# H2BR1.net
KiCad netlist of a schematic drawn in EAGLE
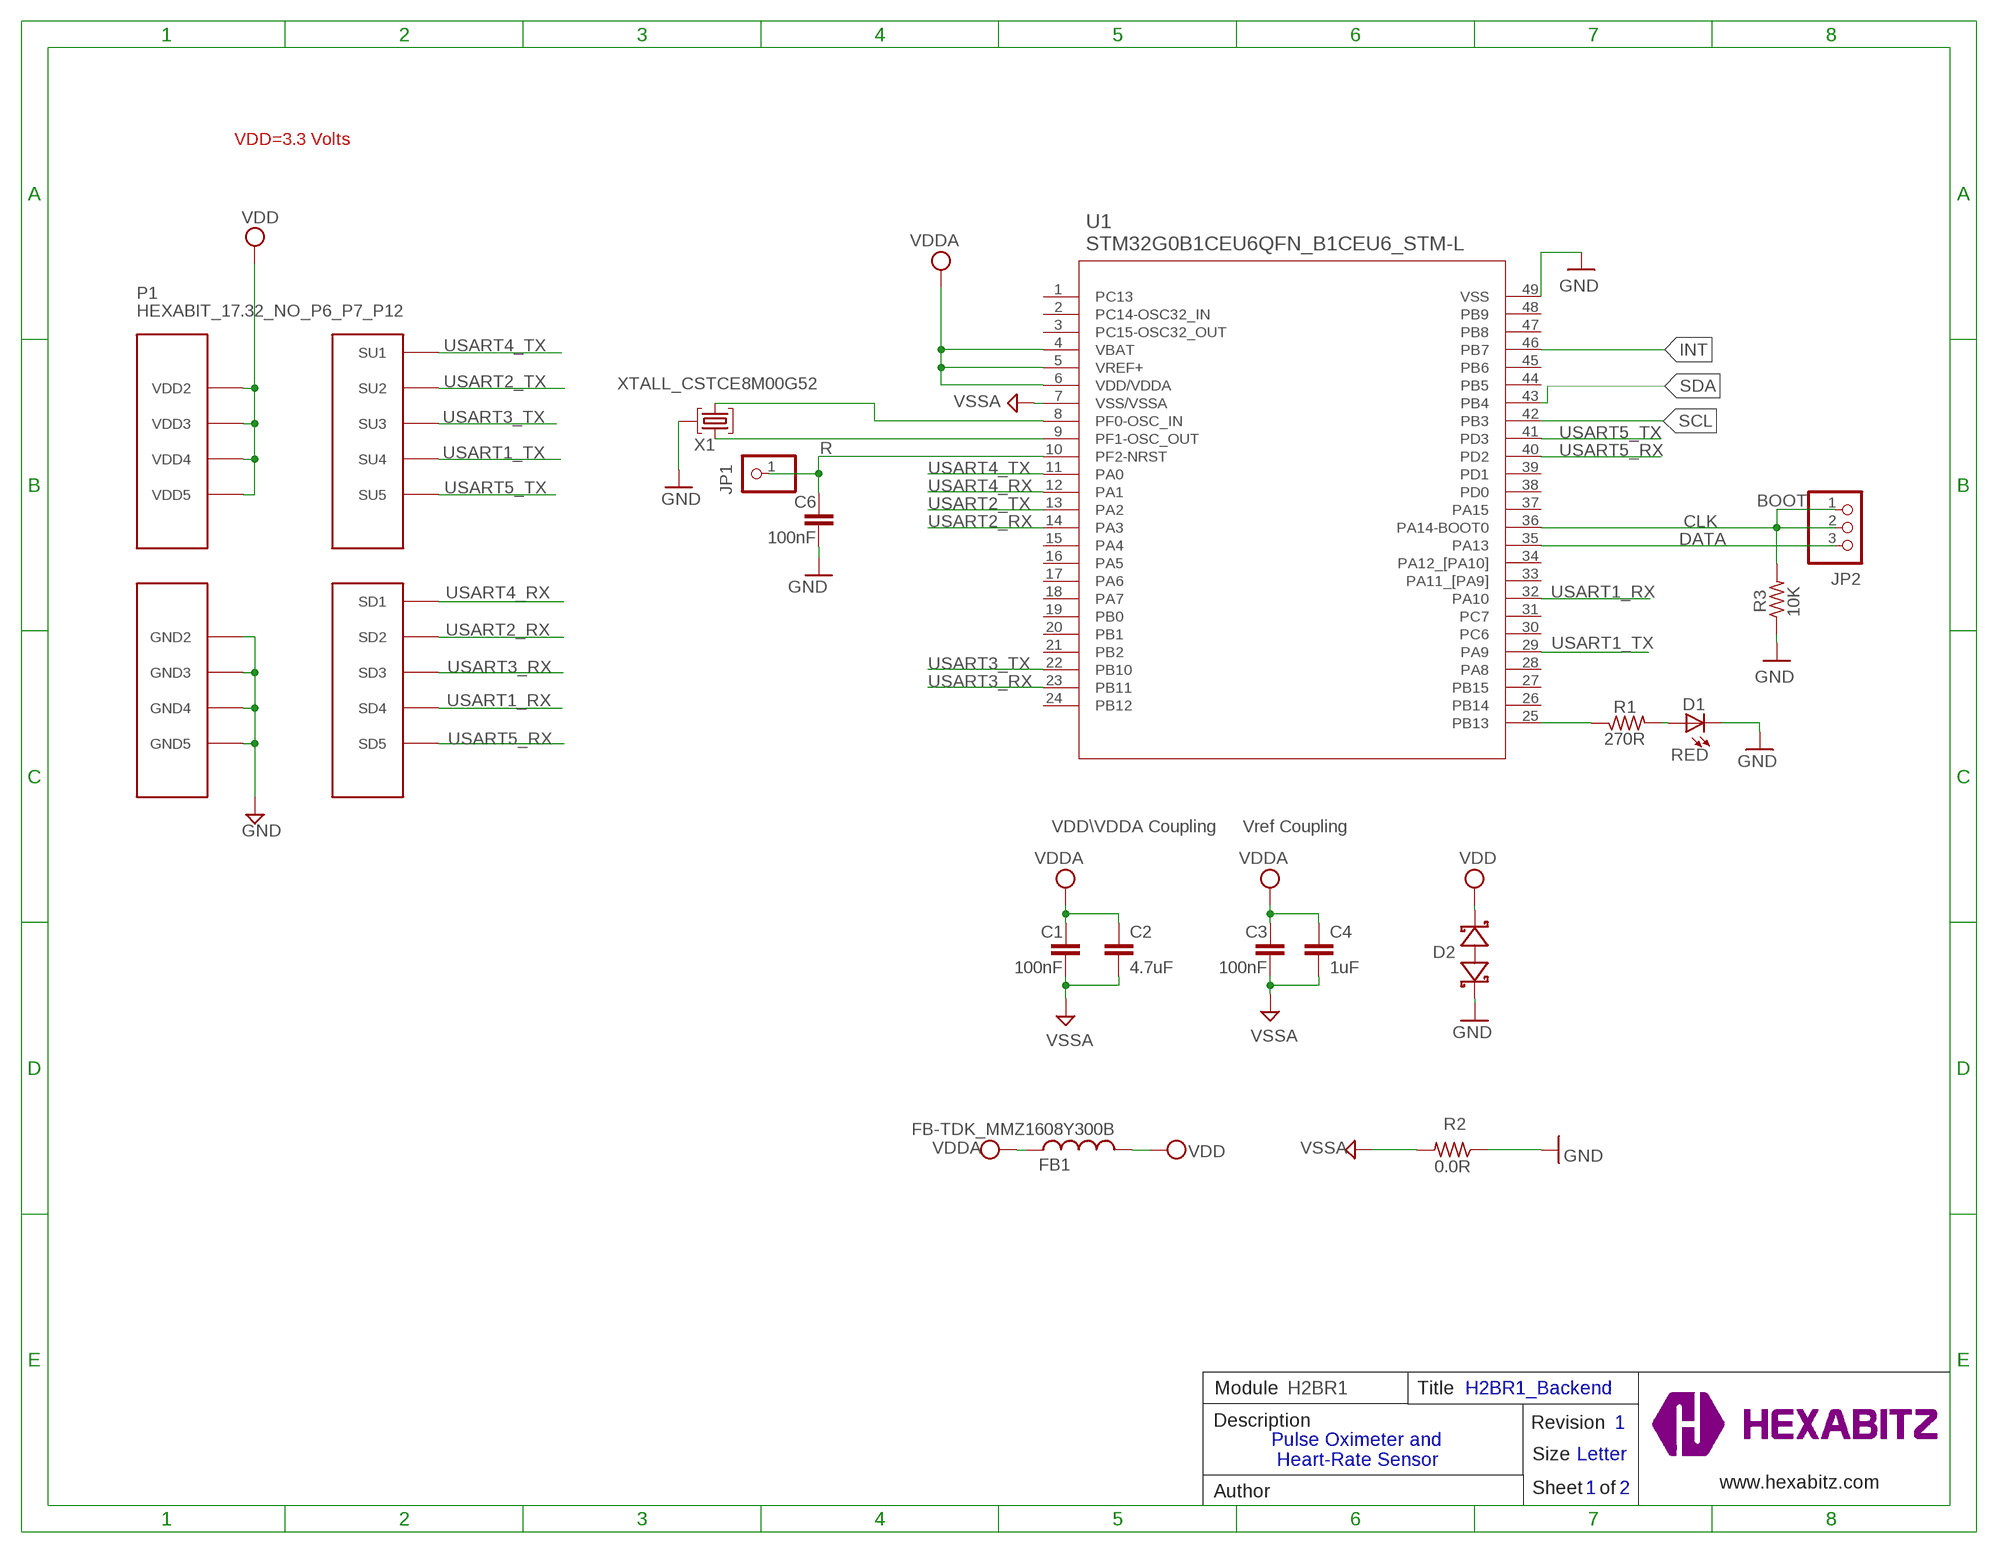
[diagram p0: schematic, sheet 1]
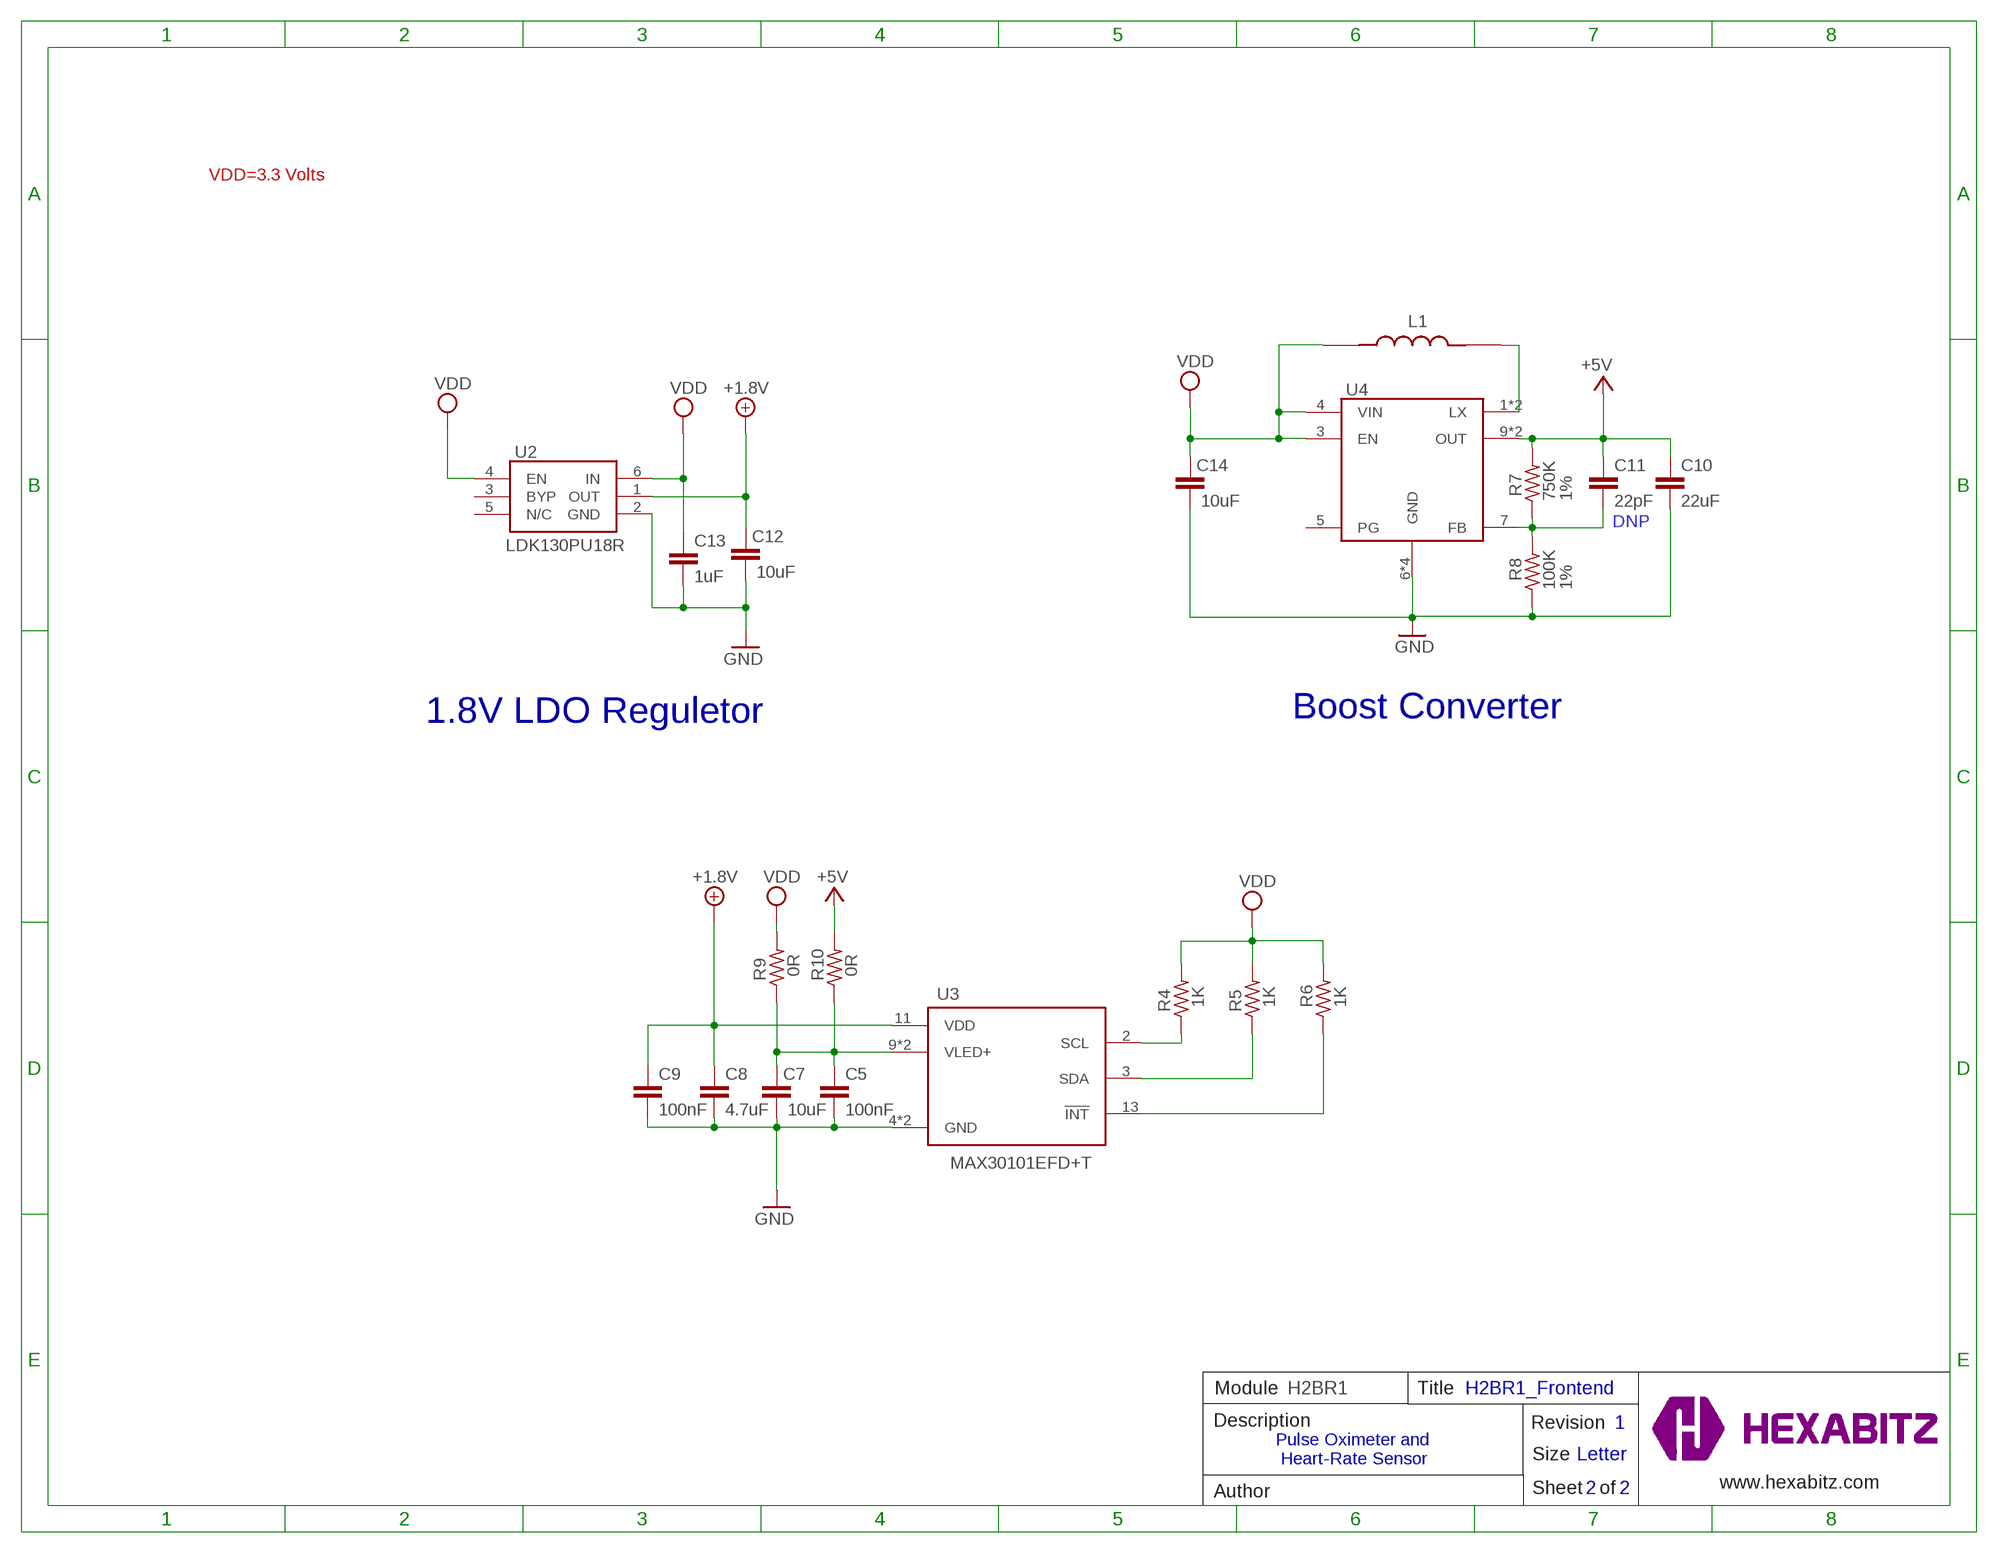
[diagram p1: schematic, sheet 2]

(export (version "E")
  (design (tool "Eeschema 10.0.6"))
  (components
    (comp (ref "C5")
      (value "100nF")
      (footprint "eagle-import:C-0603")
      (libsource (lib "eagle-import") (part "C-0603"))
    )
    (comp (ref "C7")
      (value "10uF")
      (footprint "eagle-import:C-0805")
      (libsource (lib "eagle-import") (part "C-0805"))
    )
    (comp (ref "C8")
      (value "4.7uF")
      (footprint "eagle-import:C-0805")
      (libsource (lib "eagle-import") (part "C-0805"))
    )
    (comp (ref "C9")
      (value "100nF")
      (footprint "eagle-import:C-0603")
      (libsource (lib "eagle-import") (part "C-0603"))
    )
    (comp (ref "C10")
      (value "22uF")
      (footprint "eagle-import:C-0603")
      (libsource (lib "eagle-import") (part "C-0603"))
    )
    (comp (ref "C11")
      (value "22pF")
      (footprint "eagle-import:C-0603")
      (fields (field (name "STATUS") "DNP"))
      (libsource (lib "eagle-import") (part "C-0603"))
    )
    (comp (ref "C12")
      (value "10uF")
      (footprint "eagle-import:C-0805")
      (libsource (lib "eagle-import") (part "C-0805"))
    )
    (comp (ref "C13")
      (value "1uF")
      (footprint "eagle-import:C-0805")
      (libsource (lib "eagle-import") (part "C-0805"))
    )
    (comp (ref "C14")
      (value "10uF")
      (footprint "eagle-import:C-0805")
      (libsource (lib "eagle-import") (part "C-0805"))
    )
    (comp (ref "L1")
      (value "ASMPH08062R2MT")
      (footprint "eagle-import:INDC1608X95N")
      (fields (field (name "MPN") "ASMPH-0806-2R2M-T"))
      (libsource (lib "eagle-import") (part "ASMPH08062R2MT"))
    )
    (comp (ref "R4")
      (value "1K")
      (footprint "eagle-import:R-0603")
      (libsource (lib "eagle-import") (part "R-0603"))
    )
    (comp (ref "R5")
      (value "1K")
      (footprint "eagle-import:R-0603")
      (libsource (lib "eagle-import") (part "R-0603"))
    )
    (comp (ref "R6")
      (value "1K")
      (footprint "eagle-import:R-0603")
      (libsource (lib "eagle-import") (part "R-0603"))
    )
    (comp (ref "R7")
      (value "750K")
      (footprint "eagle-import:R-0603")
      (fields (field (name "TOLERANCE") "1%"))
      (libsource (lib "eagle-import") (part "R-0603"))
    )
    (comp (ref "R8")
      (value "100K")
      (footprint "eagle-import:R-0603")
      (fields (field (name "TOLERANCE") "1%"))
      (libsource (lib "eagle-import") (part "R-0603"))
    )
    (comp (ref "R9")
      (value "0R")
      (footprint "eagle-import:R-0603")
      (libsource (lib "eagle-import") (part "R-0603"))
    )
    (comp (ref "R10")
      (value "0R")
      (footprint "eagle-import:R-0603")
      (libsource (lib "eagle-import") (part "R-0603"))
    )
    (comp (ref "U2")
      (value "LDK130PU18R")
      (footprint "eagle-import:LDK130PU18R")
      (fields (field (name "MOUSER_PART_NUMBER") "511-LDK130PU18R"))
      (libsource (lib "eagle-import") (part "LDK130PU18R"))
    )
    (comp (ref "U3")
      (value "MAX30101EFD+T")
      (footprint "eagle-import:14-LEAD-OESIP")
      (fields (field (name "MOUSER_PART_NUMBER") "700-MAX30101EFD+T"))
      (libsource (lib "eagle-import") (part "MAX30101EFD+T"))
    )
    (comp (ref "U4")
      (value "PAM2401YPADJ")
      (footprint "eagle-import:SON45P300X300X63-13N")
      (fields (field (name "MOUSER_PART_NUMBER") "621-PAM2401YPADJ"))
      (libsource (lib "eagle-import") (part "PAM2401YPADJ"))
    )
    (comp (ref "C1")
      (value "100nF")
      (footprint "eagle-import:C-0603")
      (libsource (lib "eagle-import") (part "C-0603"))
    )
    (comp (ref "C2")
      (value "4.7uF")
      (footprint "eagle-import:C-0805")
      (libsource (lib "eagle-import") (part "C-0805"))
    )
    (comp (ref "C3")
      (value "100nF")
      (footprint "eagle-import:C-0603")
      (libsource (lib "eagle-import") (part "C-0603"))
    )
    (comp (ref "C4")
      (value "1uF")
      (footprint "eagle-import:C-0805")
      (libsource (lib "eagle-import") (part "C-0805"))
    )
    (comp (ref "C6")
      (value "100nF")
      (footprint "eagle-import:C-0603")
      (libsource (lib "eagle-import") (part "C-0603"))
    )
    (comp (ref "D1")
      (value "RED")
      (footprint "eagle-import:VLMS1300-GS08")
      (fields
        (field (name "MPN") "VLMS1300-GS08")
        (field (name "MFN") "Vishay")
        (field (name "MPN_1") "VLMS1300-GS08")
        (field (name "OCTOPART_URL") "https://octopart.com/vlms1300-gs08-vishay-21709201?r=sp&s=_gcP4_q8T1SC6PJQPTQ9yA")
      )
      (libsource (lib "eagle-import") (part "VLMS1300-GS08"))
    )
    (comp (ref "D2")
      (value "BOURNS_CDSOD323-T03SCBOURNS_CDSOD323-T03SC_0_0")
      (footprint "eagle-import:BOURNS_CDSOD323-T03SC_0")
      (fields (field (name "MPN") "CDSOD323-T03SC"))
      (libsource (lib "eagle-import") (part "BOURNS_CDSOD323-T03SCBOURNS_CDSOD323-T03SC_0_0"))
    )
    (comp (ref "FB1")
      (value "FB-TDK_MMZ1608Y300B")
      (footprint "eagle-import:FB-0603")
      (fields
        (field (name "MFN") "TDK ")
        (field (name "MPN") "MMZ1608Y300B")
        (field (name "OCTOPART_URL") "https://octopart.com/mmz1608y300b-tdk-368280?r=sp&s=cd9_2ZEqQ9q9UNBuQgHAiA")
      )
      (libsource (lib "eagle-import") (part "FB-0603"))
    )
    (comp (ref "JP1")
      (value "R")
      (footprint "eagle-import:1X01")
      (fields (field (name "MPN") "87227-1"))
      (libsource (lib "eagle-import") (part "PINHD-1X1"))
    )
    (comp (ref "JP2")
      (value "PINHD-1X3")
      (footprint "eagle-import:1X03")
      (libsource (lib "eagle-import") (part "PINHD-1X3"))
    )
    (comp (ref "P1")
      (value "HEXABIT_17.32_NO_P6_P7_P12")
      (footprint "eagle-import:HEXABIT_17.32_NO_P6_P7_P12")
      (libsource (lib "eagle-import") (part "HEXABIT_?_NO_P6_P7_P1217.32"))
    )
    (comp (ref "R1")
      (value "270R")
      (footprint "eagle-import:R-0603")
      (libsource (lib "eagle-import") (part "R-0603"))
    )
    (comp (ref "R2")
      (value "0.0R")
      (footprint "eagle-import:R-0603")
      (fields
        (field (name "MFN") "Yageo")
        (field (name "MPN") "RC0603JR-070RL")
        (field (name "OCTOPART_URL") "https://octopart.com/rc0603jr-070rl-yageo-1241539?r=sp&s=X2NteqRjRNWrnx42Y0aliA")
        (field (name "RESISTANCE") "0.0 Ohm")
      )
      (libsource (lib "eagle-import") (part "R-0603"))
    )
    (comp (ref "R3")
      (value "10K")
      (footprint "eagle-import:R-0603")
      (libsource (lib "eagle-import") (part "R-0603"))
    )
    (comp (ref "TRIMBLE-LOGO1")
      (value "HEXA-LOGO")
      (footprint "eagle-import:HEXA-LOGO")
      (libsource (lib "eagle-import") (part "HEXA-LOGO"))
    )
    (comp (ref "U1")
      (value "STM32G0B1CEU6QFN_B1CEU6_STM-L")
      (footprint "eagle-import:QFN_B1CEU6_STM-L")
      (fields
        (field (name "MANUFACTURER_PART_NUMBER") "STM32G0B1CEU6")
        (field (name "COPYRIGHT") "Copyright (C) 2021 Ultra Librarian. All rights reserved.")
      )
      (libsource (lib "eagle-import") (part "STM32G0B1CEU6QFN_B1CEU6_STM-L"))
    )
    (comp (ref "X1")
      (value "XTALL_CSTCE8M00G52")
      (footprint "eagle-import:XTALL_CSTCE8M00G52")
      (fields (field (name "MPN") "CSTCE8M00G52Z-R0"))
      (libsource (lib "eagle-import") (part "XTALL_CSTCE8M00G52"))
    )
  )
  (nets
    (net (code "1") (name "+1.8V") (class "Default")
      (node (ref "C12") (pin "1") (pinfunction "1_1") (pintype "passive"))
      (node (ref "C8") (pin "1") (pinfunction "1_1") (pintype "passive"))
      (node (ref "C9") (pin "1") (pinfunction "1_1") (pintype "passive"))
      (node (ref "U2") (pin "1") (pinfunction "OUT_1") (pintype "bidirectional"))
      (node (ref "U3") (pin "11") (pinfunction "VDD_11") (pintype "bidirectional"))
    )
    (net (code "2") (name "+5V") (class "Default")
      (node (ref "C10") (pin "1") (pinfunction "1_1") (pintype "passive"))
      (node (ref "C11") (pin "1") (pinfunction "1_1") (pintype "passive"))
      (node (ref "R10") (pin "2") (pinfunction "2_2") (pintype "passive"))
      (node (ref "R7") (pin "2") (pinfunction "2_2") (pintype "passive"))
      (node (ref "U4") (pin "10") (pinfunction "OUT_10") (pintype "bidirectional"))
      (node (ref "U4") (pin "9") (pinfunction "OUT_9") (pintype "bidirectional"))
    )
    (net (code "3") (name "CLK") (class "Default")
      (node (ref "JP2") (pin "1") (pinfunction "1_1") (pintype "passive"))
      (node (ref "JP2") (pin "2") (pinfunction "2_2") (pintype "passive"))
      (node (ref "R3") (pin "2") (pinfunction "2_2") (pintype "passive"))
      (node (ref "U1") (pin "36") (pinfunction "PA14-BOOT0_36") (pintype "bidirectional"))
    )
    (net (code "4") (name "DATA") (class "Default")
      (node (ref "JP2") (pin "3") (pinfunction "3_3") (pintype "passive"))
      (node (ref "U1") (pin "35") (pinfunction "PA13_35") (pintype "bidirectional"))
    )
    (net (code "5") (name "GND") (class "Default")
      (node (ref "C10") (pin "2") (pinfunction "2_2") (pintype "passive"))
      (node (ref "C12") (pin "2") (pinfunction "2_2") (pintype "passive"))
      (node (ref "C13") (pin "2") (pinfunction "2_2") (pintype "passive"))
      (node (ref "C14") (pin "2") (pinfunction "2_2") (pintype "passive"))
      (node (ref "C5") (pin "2") (pinfunction "2_2") (pintype "passive"))
      (node (ref "C6") (pin "2") (pinfunction "2_2") (pintype "passive"))
      (node (ref "C7") (pin "2") (pinfunction "2_2") (pintype "passive"))
      (node (ref "C8") (pin "2") (pinfunction "2_2") (pintype "passive"))
      (node (ref "C9") (pin "2") (pinfunction "2_2") (pintype "passive"))
      (node (ref "D1") (pin "C") (pinfunction "C_C") (pintype "passive"))
      (node (ref "D2") (pin "1") (pinfunction "A_1") (pintype "passive"))
      (node (ref "P1") (pin "PAD_PD10") (pinfunction "GND4_PAD_PD10") (pintype "power_in"))
      (node (ref "P1") (pin "PAD_PD11") (pinfunction "GND5_PAD_PD11") (pintype "power_in"))
      (node (ref "P1") (pin "PAD_PD8") (pinfunction "GND2_PAD_PD8") (pintype "power_in"))
      (node (ref "P1") (pin "PAD_PD9") (pinfunction "GND3_PAD_PD9") (pintype "power_in"))
      (node (ref "R2") (pin "1") (pinfunction "1_1") (pintype "passive"))
      (node (ref "R3") (pin "1") (pinfunction "1_1") (pintype "passive"))
      (node (ref "R8") (pin "1") (pinfunction "1_1") (pintype "passive"))
      (node (ref "U1") (pin "49") (pinfunction "VSS_49") (pintype "passive"))
      (node (ref "U2") (pin "2") (pinfunction "GND_2") (pintype "bidirectional"))
      (node (ref "U3") (pin "12") (pinfunction "GND_12") (pintype "bidirectional"))
      (node (ref "U3") (pin "4") (pinfunction "GND_4") (pintype "bidirectional"))
      (node (ref "U4") (pin "11") (pinfunction "GND_11") (pintype "bidirectional"))
      (node (ref "U4") (pin "12") (pinfunction "GND_12") (pintype "bidirectional"))
      (node (ref "U4") (pin "13") (pinfunction "GND_13") (pintype "bidirectional"))
      (node (ref "U4") (pin "6") (pinfunction "GND_6") (pintype "bidirectional"))
      (node (ref "X1") (pin "P$2") (pinfunction "2_P$2") (pintype "passive"))
    )
    (net (code "6") (name "INT") (class "Default")
      (node (ref "R6") (pin "1") (pinfunction "1_1") (pintype "passive"))
      (node (ref "U1") (pin "46") (pinfunction "PB7_46") (pintype "bidirectional"))
      (node (ref "U3") (pin "13") (pinfunction "~{INT}_13") (pintype "bidirectional"))
    )
    (net (code "7") (name "Net-(C5-Pad1)") (class "Default")
      (node (ref "C5") (pin "1") (pinfunction "1_1") (pintype "passive"))
      (node (ref "C7") (pin "1") (pinfunction "1_1") (pintype "passive"))
      (node (ref "R10") (pin "1") (pinfunction "1_1") (pintype "passive"))
      (node (ref "R9") (pin "1") (pinfunction "1_1") (pintype "passive"))
      (node (ref "U3") (pin "10") (pinfunction "VLED+_10") (pintype "bidirectional"))
      (node (ref "U3") (pin "9") (pinfunction "VLED+_9") (pintype "bidirectional"))
    )
    (net (code "8") (name "Net-(D1-PadA)") (class "Default")
      (node (ref "D1") (pin "A") (pinfunction "A_A") (pintype "passive"))
      (node (ref "R1") (pin "2") (pinfunction "2_2") (pintype "passive"))
    )
    (net (code "9") (name "Net-(L1-Pad2)") (class "Default")
      (node (ref "L1") (pin "2") (pinfunction "2_2") (pintype "passive"))
      (node (ref "U4") (pin "1") (pinfunction "LX_1") (pintype "bidirectional"))
      (node (ref "U4") (pin "2") (pinfunction "LX_2") (pintype "bidirectional"))
    )
    (net (code "10") (name "Net-(U1-PB13)") (class "Default")
      (node (ref "R1") (pin "1") (pinfunction "1_1") (pintype "passive"))
      (node (ref "U1") (pin "25") (pinfunction "PB13_25") (pintype "bidirectional"))
    )
    (net (code "11") (name "Net-(U1-PF0-OSC_IN)") (class "Default")
      (node (ref "U1") (pin "8") (pinfunction "PF0-OSC_IN_8") (pintype "bidirectional"))
      (node (ref "X1") (pin "P$3") (pinfunction "3_P$3") (pintype "passive"))
    )
    (net (code "12") (name "Net-(U1-PF1-OSC_OUT)") (class "Default")
      (node (ref "U1") (pin "9") (pinfunction "PF1-OSC_OUT_9") (pintype "output"))
      (node (ref "X1") (pin "P$1") (pinfunction "1_P$1") (pintype "passive"))
    )
    (net (code "13") (name "Net-(U1-PF2-NRST)") (class "Default")
      (node (ref "C6") (pin "1") (pinfunction "1_1") (pintype "passive"))
      (node (ref "JP1") (pin "1") (pinfunction "1_1") (pintype "passive"))
      (node (ref "U1") (pin "10") (pinfunction "PF2-NRST_10") (pintype "bidirectional"))
    )
    (net (code "14") (name "Net-(U4-FB)") (class "Default")
      (node (ref "C11") (pin "2") (pinfunction "2_2") (pintype "passive"))
      (node (ref "R7") (pin "1") (pinfunction "1_1") (pintype "passive"))
      (node (ref "R8") (pin "2") (pinfunction "2_2") (pintype "passive"))
      (node (ref "U4") (pin "7") (pinfunction "FB_7") (pintype "bidirectional"))
    )
    (net (code "15") (name "SCL") (class "Default")
      (node (ref "R4") (pin "1") (pinfunction "1_1") (pintype "passive"))
      (node (ref "U1") (pin "42") (pinfunction "PB3_42") (pintype "bidirectional"))
      (node (ref "U3") (pin "2") (pinfunction "SCL_2") (pintype "bidirectional"))
    )
    (net (code "16") (name "SDA") (class "Default")
      (node (ref "R5") (pin "1") (pinfunction "1_1") (pintype "passive"))
      (node (ref "U1") (pin "43") (pinfunction "PB4_43") (pintype "bidirectional"))
      (node (ref "U3") (pin "3") (pinfunction "SDA_3") (pintype "bidirectional"))
    )
    (net (code "17") (name "USART1_RX") (class "Default")
      (node (ref "P1") (pin "PAD_PD4") (pinfunction "SD4_PAD_PD4") (pintype "bidirectional"))
      (node (ref "U1") (pin "32") (pinfunction "PA10_32") (pintype "bidirectional"))
    )
    (net (code "18") (name "USART1_TX") (class "Default")
      (node (ref "P1") (pin "PAD_PU4") (pinfunction "SU4_PAD_PU4") (pintype "bidirectional"))
      (node (ref "U1") (pin "29") (pinfunction "PA9_29") (pintype "bidirectional"))
    )
    (net (code "19") (name "USART2_RX") (class "Default")
      (node (ref "P1") (pin "PAD_PD2") (pinfunction "SD2_PAD_PD2") (pintype "bidirectional"))
      (node (ref "U1") (pin "14") (pinfunction "PA3_14") (pintype "bidirectional"))
    )
    (net (code "20") (name "USART2_TX") (class "Default")
      (node (ref "P1") (pin "PAD_PU2") (pinfunction "SU2_PAD_PU2") (pintype "bidirectional"))
      (node (ref "U1") (pin "13") (pinfunction "PA2_13") (pintype "bidirectional"))
    )
    (net (code "21") (name "USART3_RX") (class "Default")
      (node (ref "P1") (pin "PAD_PD3") (pinfunction "SD3_PAD_PD3") (pintype "bidirectional"))
      (node (ref "U1") (pin "23") (pinfunction "PB11_23") (pintype "bidirectional"))
    )
    (net (code "22") (name "USART3_TX") (class "Default")
      (node (ref "P1") (pin "PAD_PU3") (pinfunction "SU3_PAD_PU3") (pintype "bidirectional"))
      (node (ref "U1") (pin "22") (pinfunction "PB10_22") (pintype "bidirectional"))
    )
    (net (code "23") (name "USART4_RX") (class "Default")
      (node (ref "P1") (pin "PAD_PD1") (pinfunction "SD1_PAD_PD1") (pintype "bidirectional"))
      (node (ref "U1") (pin "12") (pinfunction "PA1_12") (pintype "bidirectional"))
    )
    (net (code "24") (name "USART4_TX") (class "Default")
      (node (ref "P1") (pin "PAD_PU1") (pinfunction "SU1_PAD_PU1") (pintype "bidirectional"))
      (node (ref "U1") (pin "11") (pinfunction "PA0_11") (pintype "bidirectional"))
    )
    (net (code "25") (name "USART5_RX") (class "Default")
      (node (ref "P1") (pin "PAD_PD5") (pinfunction "SD5_PAD_PD5") (pintype "bidirectional"))
      (node (ref "U1") (pin "40") (pinfunction "PD2_40") (pintype "bidirectional"))
    )
    (net (code "26") (name "USART5_TX") (class "Default")
      (node (ref "P1") (pin "PAD_PU5") (pinfunction "SU5_PAD_PU5") (pintype "bidirectional"))
      (node (ref "U1") (pin "41") (pinfunction "PD3_41") (pintype "bidirectional"))
    )
    (net (code "27") (name "VDD") (class "Default")
      (node (ref "C13") (pin "1") (pinfunction "1_1") (pintype "passive"))
      (node (ref "C14") (pin "1") (pinfunction "1_1") (pintype "passive"))
      (node (ref "D2") (pin "2") (pinfunction "C_2") (pintype "passive"))
      (node (ref "FB1") (pin "2") (pinfunction "2_2") (pintype "passive"))
      (node (ref "L1") (pin "1") (pinfunction "1_1") (pintype "passive"))
      (node (ref "P1") (pin "PAD_PU10") (pinfunction "VDD4_PAD_PU10") (pintype "power_in"))
      (node (ref "P1") (pin "PAD_PU11") (pinfunction "VDD5_PAD_PU11") (pintype "power_in"))
      (node (ref "P1") (pin "PAD_PU8") (pinfunction "VDD2_PAD_PU8") (pintype "power_in"))
      (node (ref "P1") (pin "PAD_PU9") (pinfunction "VDD3_PAD_PU9") (pintype "power_in"))
      (node (ref "R4") (pin "2") (pinfunction "2_2") (pintype "passive"))
      (node (ref "R5") (pin "2") (pinfunction "2_2") (pintype "passive"))
      (node (ref "R6") (pin "2") (pinfunction "2_2") (pintype "passive"))
      (node (ref "R9") (pin "2") (pinfunction "2_2") (pintype "passive"))
      (node (ref "U2") (pin "4") (pinfunction "EN_4") (pintype "bidirectional"))
      (node (ref "U2") (pin "6") (pinfunction "IN_6") (pintype "bidirectional"))
      (node (ref "U4") (pin "3") (pinfunction "EN_3") (pintype "bidirectional"))
      (node (ref "U4") (pin "4") (pinfunction "VIN_4") (pintype "bidirectional"))
    )
    (net (code "28") (name "VDDA") (class "Default")
      (node (ref "C1") (pin "1") (pinfunction "1_1") (pintype "passive"))
      (node (ref "C2") (pin "1") (pinfunction "1_1") (pintype "passive"))
      (node (ref "C3") (pin "1") (pinfunction "1_1") (pintype "passive"))
      (node (ref "C4") (pin "1") (pinfunction "1_1") (pintype "passive"))
      (node (ref "FB1") (pin "1") (pinfunction "1_1") (pintype "passive"))
      (node (ref "U1") (pin "4") (pinfunction "VBAT_4") (pintype "passive"))
      (node (ref "U1") (pin "5") (pinfunction "VREF+_5") (pintype "power_in"))
      (node (ref "U1") (pin "6") (pinfunction "VDD/VDDA_6") (pintype "power_in"))
    )
    (net (code "29") (name "VSSA") (class "Default")
      (node (ref "C1") (pin "2") (pinfunction "2_2") (pintype "passive"))
      (node (ref "C2") (pin "2") (pinfunction "2_2") (pintype "passive"))
      (node (ref "C3") (pin "2") (pinfunction "2_2") (pintype "passive"))
      (node (ref "C4") (pin "2") (pinfunction "2_2") (pintype "passive"))
      (node (ref "R2") (pin "2") (pinfunction "2_2") (pintype "passive"))
      (node (ref "U1") (pin "7") (pinfunction "VSS/VSSA_7") (pintype "passive"))
    )
    (net (code "30") (name "unconnected-(U1-PA4-Pad15)") (class "Default")
      (node (ref "U1") (pin "15") (pinfunction "PA4_15") (pintype "bidirectional"))
    )
    (net (code "31") (name "unconnected-(U1-PA5-Pad16)") (class "Default")
      (node (ref "U1") (pin "16") (pinfunction "PA5_16") (pintype "bidirectional"))
    )
    (net (code "32") (name "unconnected-(U1-PA6-Pad17)") (class "Default")
      (node (ref "U1") (pin "17") (pinfunction "PA6_17") (pintype "bidirectional"))
    )
    (net (code "33") (name "unconnected-(U1-PA7-Pad18)") (class "Default")
      (node (ref "U1") (pin "18") (pinfunction "PA7_18") (pintype "bidirectional"))
    )
    (net (code "34") (name "unconnected-(U1-PA8-Pad28)") (class "Default")
      (node (ref "U1") (pin "28") (pinfunction "PA8_28") (pintype "bidirectional"))
    )
    (net (code "35") (name "unconnected-(U1-PA11_[PA9]-Pad33)") (class "Default")
      (node (ref "U1") (pin "33") (pinfunction "PA11_[PA9]_33") (pintype "bidirectional"))
    )
    (net (code "36") (name "unconnected-(U1-PA12_[PA10]-Pad34)") (class "Default")
      (node (ref "U1") (pin "34") (pinfunction "PA12_[PA10]_34") (pintype "bidirectional"))
    )
    (net (code "37") (name "unconnected-(U1-PA15-Pad37)") (class "Default")
      (node (ref "U1") (pin "37") (pinfunction "PA15_37") (pintype "bidirectional"))
    )
    (net (code "38") (name "unconnected-(U1-PB0-Pad19)") (class "Default")
      (node (ref "U1") (pin "19") (pinfunction "PB0_19") (pintype "bidirectional"))
    )
    (net (code "39") (name "unconnected-(U1-PB1-Pad20)") (class "Default")
      (node (ref "U1") (pin "20") (pinfunction "PB1_20") (pintype "bidirectional"))
    )
    (net (code "40") (name "unconnected-(U1-PB2-Pad21)") (class "Default")
      (node (ref "U1") (pin "21") (pinfunction "PB2_21") (pintype "bidirectional"))
    )
    (net (code "41") (name "unconnected-(U1-PB5-Pad44)") (class "Default")
      (node (ref "U1") (pin "44") (pinfunction "PB5_44") (pintype "bidirectional"))
    )
    (net (code "42") (name "unconnected-(U1-PB6-Pad45)") (class "Default")
      (node (ref "U1") (pin "45") (pinfunction "PB6_45") (pintype "bidirectional"))
    )
    (net (code "43") (name "unconnected-(U1-PB8-Pad47)") (class "Default")
      (node (ref "U1") (pin "47") (pinfunction "PB8_47") (pintype "bidirectional"))
    )
    (net (code "44") (name "unconnected-(U1-PB9-Pad48)") (class "Default")
      (node (ref "U1") (pin "48") (pinfunction "PB9_48") (pintype "bidirectional"))
    )
    (net (code "45") (name "unconnected-(U1-PB12-Pad24)") (class "Default")
      (node (ref "U1") (pin "24") (pinfunction "PB12_24") (pintype "bidirectional"))
    )
    (net (code "46") (name "unconnected-(U1-PB14-Pad26)") (class "Default")
      (node (ref "U1") (pin "26") (pinfunction "PB14_26") (pintype "bidirectional"))
    )
    (net (code "47") (name "unconnected-(U1-PB15-Pad27)") (class "Default")
      (node (ref "U1") (pin "27") (pinfunction "PB15_27") (pintype "bidirectional"))
    )
    (net (code "48") (name "unconnected-(U1-PC6-Pad30)") (class "Default")
      (node (ref "U1") (pin "30") (pinfunction "PC6_30") (pintype "bidirectional"))
    )
    (net (code "49") (name "unconnected-(U1-PC7-Pad31)") (class "Default")
      (node (ref "U1") (pin "31") (pinfunction "PC7_31") (pintype "bidirectional"))
    )
    (net (code "50") (name "unconnected-(U1-PC13-Pad1)") (class "Default")
      (node (ref "U1") (pin "1") (pinfunction "PC13_1") (pintype "bidirectional"))
    )
    (net (code "51") (name "unconnected-(U1-PC14-OSC32_IN-Pad2)") (class "Default")
      (node (ref "U1") (pin "2") (pinfunction "PC14-OSC32_IN_2") (pintype "bidirectional"))
    )
    (net (code "52") (name "unconnected-(U1-PC15-OSC32_OUT-Pad3)") (class "Default")
      (node (ref "U1") (pin "3") (pinfunction "PC15-OSC32_OUT_3") (pintype "output"))
    )
    (net (code "53") (name "unconnected-(U1-PD0-Pad38)") (class "Default")
      (node (ref "U1") (pin "38") (pinfunction "PD0_38") (pintype "bidirectional"))
    )
    (net (code "54") (name "unconnected-(U1-PD1-Pad39)") (class "Default")
      (node (ref "U1") (pin "39") (pinfunction "PD1_39") (pintype "bidirectional"))
    )
    (net (code "55") (name "unconnected-(U2-BYP-Pad3)") (class "Default")
      (node (ref "U2") (pin "3") (pinfunction "BYP_3") (pintype "no_connect"))
    )
    (net (code "56") (name "unconnected-(U2-N{slash}C-Pad5)") (class "Default")
      (node (ref "U2") (pin "5") (pinfunction "N/C_5") (pintype "no_connect"))
    )
    (net (code "57") (name "unconnected-(U4-PG-Pad5)") (class "Default")
      (node (ref "U4") (pin "5") (pinfunction "PG_5") (pintype "bidirectional"))
    )
  )
)
